# SensWear_Debug_DEBUG.net
KiCad netlist of a schematic drawn in Altium Designer
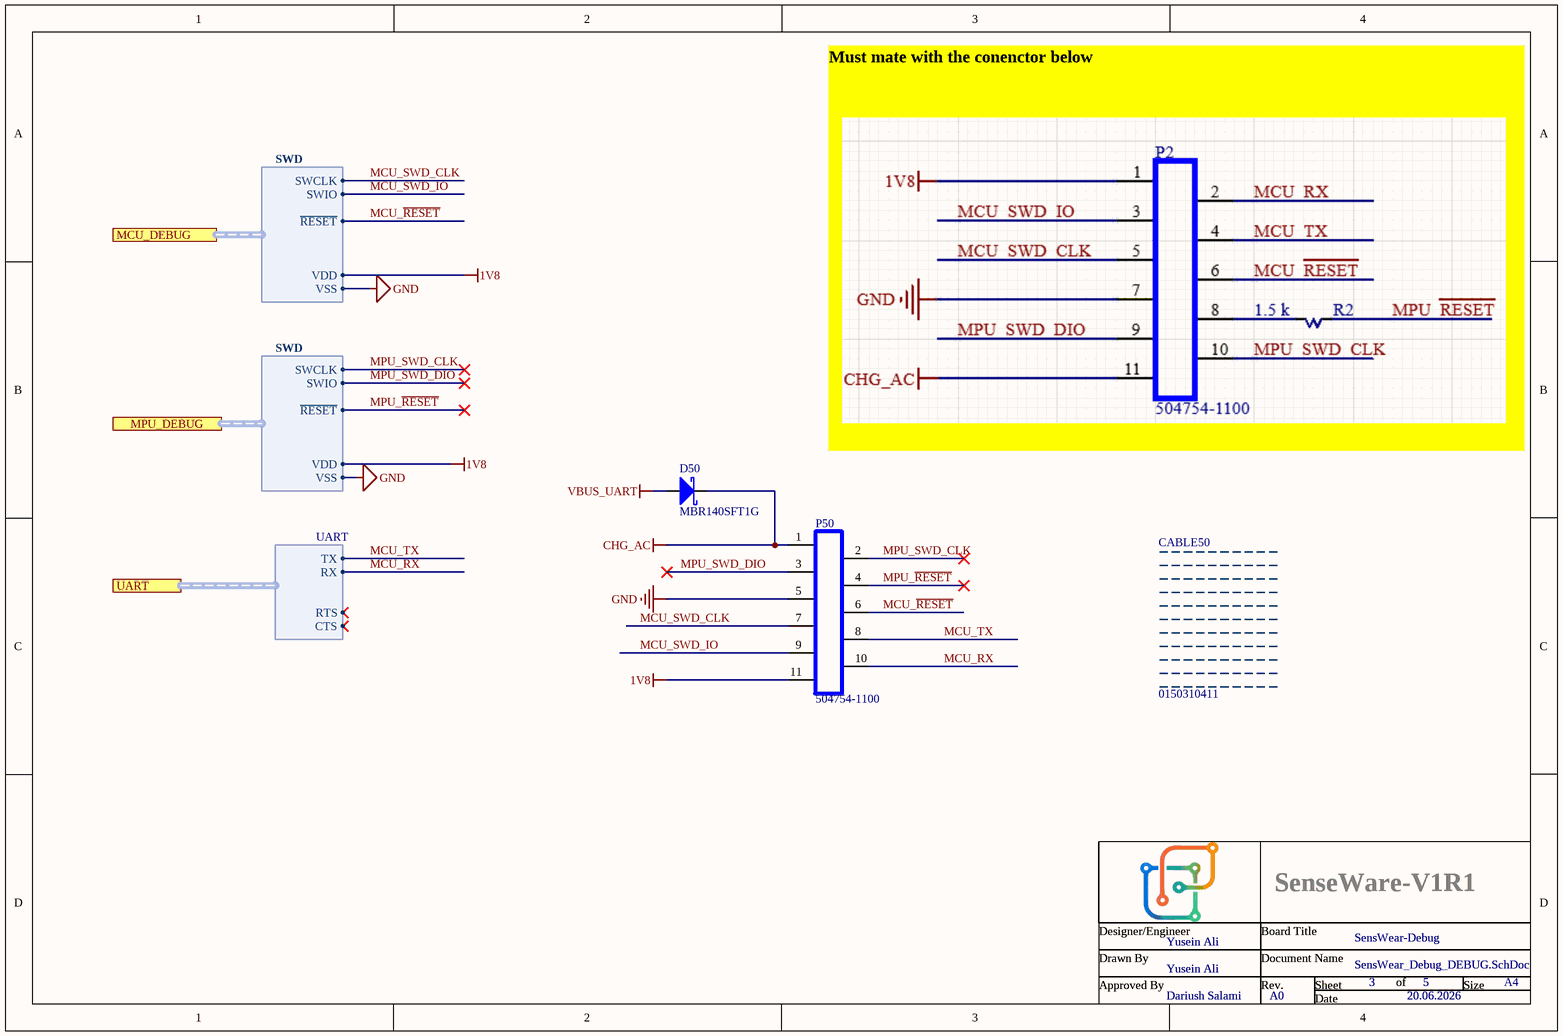
[diagram p0: SensWear_Debug_DEBUG.SchDoc]

(export (version "E")
  (design (tool "Eeschema 10.0.6"))
  (components
    (comp (ref "CABLE50")
      (value "0150310411")
      (fields (field (name "MANUFACTURER") "Molex"))
      (libsource (lib "SensWearComponents") (part "0150310411"))
    )
    (comp (ref "D50")
      (value "MBR140SFT1G")
      (footprint "SODFL360X110-2N")
      (description "DIODE SCHOTTKY 40V 1A SOD123L")
      (fields (field (name "MANUFACTURER") "ON Semiconductor"))
      (libsource (lib "SensWearComponents") (part "MBR140SFT1G"))
    )
    (comp (ref "P50")
      (value "504754-1100")
      (footprint "5047541100__3")
      (description "Conn FFC/FPC Connector SKT 11 POS 0.3mm Solder RA SMD Easy-On™ T/R")
      (fields (field (name "MANUFACTURER") "Molex") (field (name "CHECKED") "FALSE"))
      (libsource (lib "SensWearComponents") (part "504754-1100"))
    )
  )
  (nets
    (net (code "3") (name "/MCU_RX") (class "Default")
      (node (ref "P50") (pin "10") (pinfunction "10_10") (pintype "passive"))
    )
    (net (code "4") (name "/MCU_SWD_CLK") (class "Default")
      (node (ref "P50") (pin "7") (pinfunction "7_7") (pintype "passive"))
    )
    (net (code "5") (name "/MCU_SWD_IO") (class "Default")
      (node (ref "P50") (pin "9") (pinfunction "9_9") (pintype "passive"))
    )
    (net (code "6") (name "/MCU_TX") (class "Default")
      (node (ref "P50") (pin "8") (pinfunction "8_8") (pintype "passive"))
    )
    (net (code "7") (name "/MCU_~{RESET}") (class "Default")
      (node (ref "P50") (pin "6") (pinfunction "6_6") (pintype "passive"))
    )
    (net (code "8") (name "/MPU_SWD_CLK") (class "Default")
      (node (ref "P50") (pin "2") (pinfunction "2_2") (pintype "passive+no_connect"))
    )
    (net (code "9") (name "/MPU_SWD_DIO") (class "Default")
      (node (ref "P50") (pin "3") (pinfunction "3_3") (pintype "passive+no_connect"))
    )
    (net (code "10") (name "/MPU_~{RESET}") (class "Default")
      (node (ref "P50") (pin "4") (pinfunction "4_4") (pintype "passive+no_connect"))
    )
    (net (code "13") (name "1V8") (class "Default")
      (node (ref "P50") (pin "11") (pinfunction "11_11") (pintype "passive"))
    )
    (net (code "14") (name "CHG_AC") (class "Default")
      (node (ref "D50") (pin "1") (pinfunction "cathode_1") (pintype "passive"))
      (node (ref "P50") (pin "1") (pinfunction "1_1") (pintype "passive"))
    )
    (net (code "15") (name "GND") (class "Default")
      (node (ref "P50") (pin "5") (pinfunction "5_5") (pintype "passive"))
    )
    (net (code "16") (name "VBUS_UART") (class "Default")
      (node (ref "D50") (pin "2") (pinfunction "ANODE_2") (pintype "passive"))
    )
  )
)
